# sousvide2.net
KiCad netlist of a schematic drawn in EAGLE
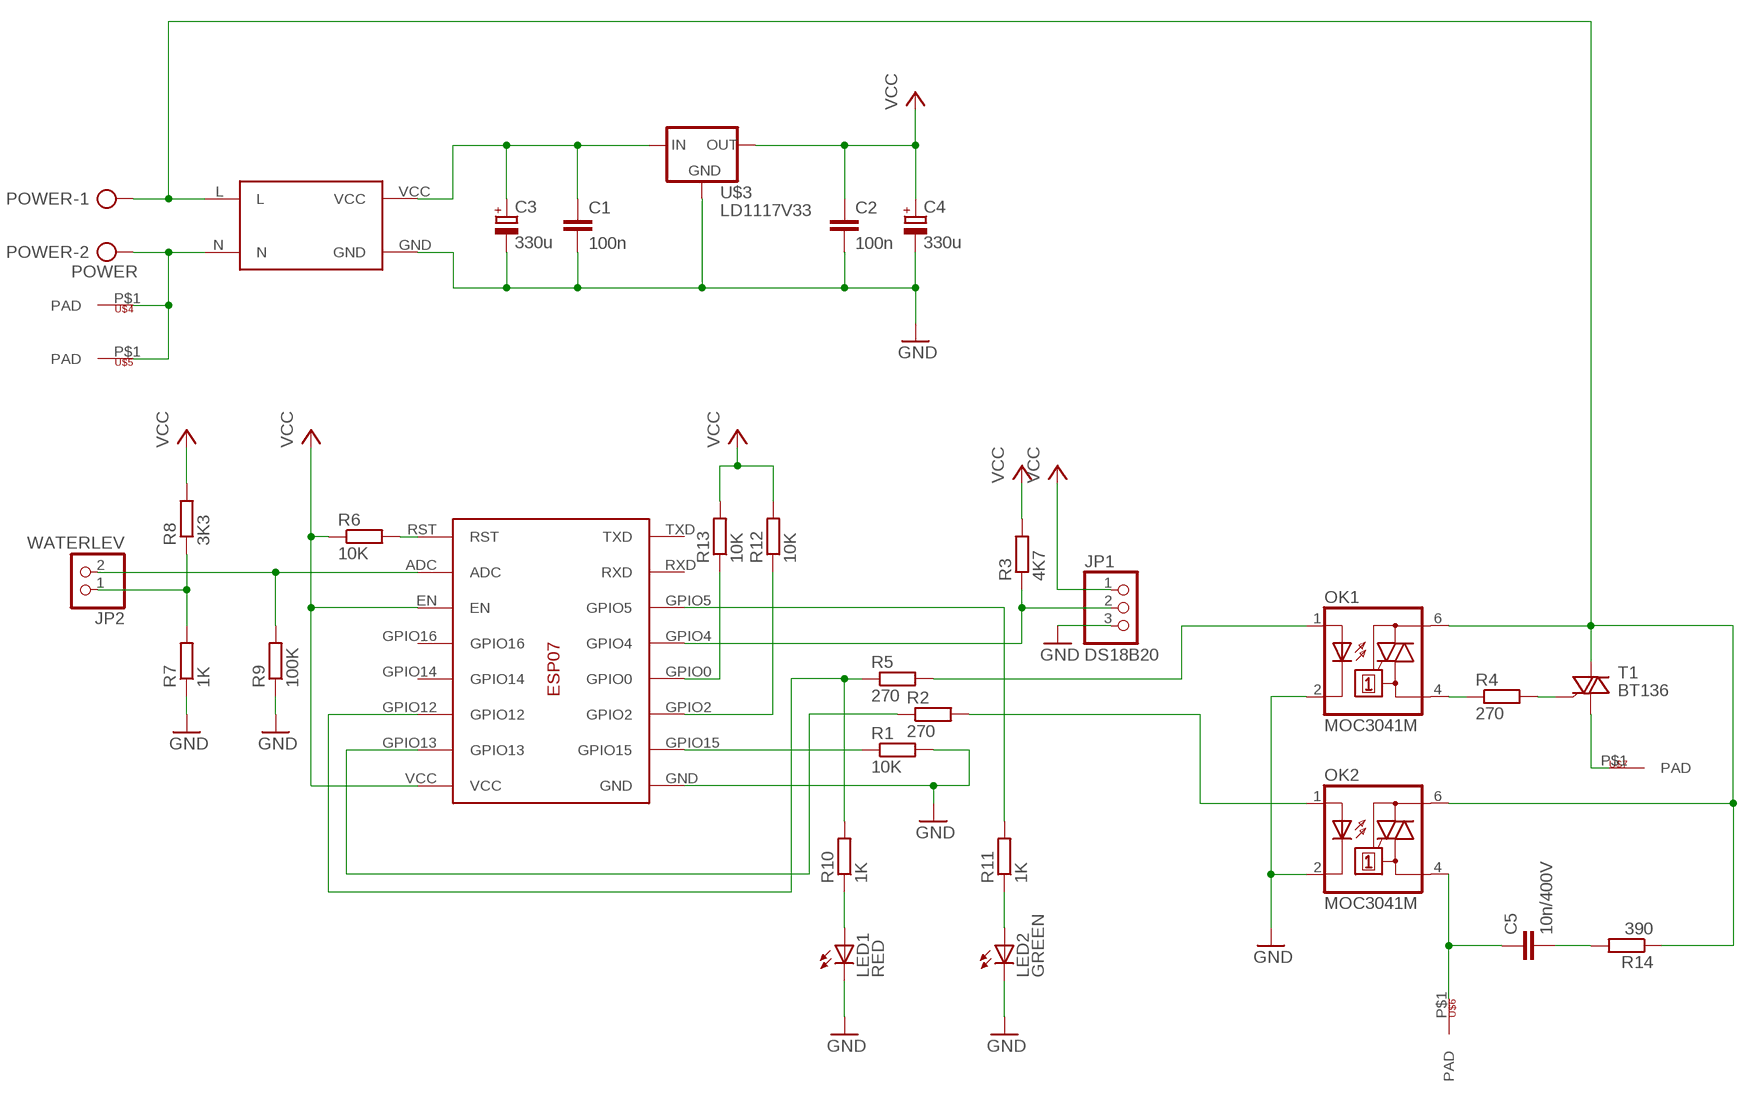
[diagram p0: schematic, sheet 1]

(export (version "E")
  (design (tool "Eeschema 10.0.6"))
  (components
    (comp (ref "C1")
      (value "100n")
      (footprint "eagle-import:C050-025X075")
      (libsource (lib "eagle-import") (part "C-EU050-025X075"))
    )
    (comp (ref "C2")
      (value "100n")
      (footprint "eagle-import:C050-025X075")
      (libsource (lib "eagle-import") (part "C-EU050-025X075"))
    )
    (comp (ref "C3")
      (value "330u")
      (footprint "eagle-import:E2,5-6")
      (libsource (lib "eagle-import") (part "CPOL-EUE2.5-6"))
    )
    (comp (ref "C4")
      (value "330u")
      (footprint "eagle-import:E2,5-6")
      (libsource (lib "eagle-import") (part "CPOL-EUE2.5-6"))
    )
    (comp (ref "C5")
      (value "10n/400V")
      (footprint "eagle-import:C102-064X133")
      (libsource (lib "eagle-import") (part "resistor_C-EU102-064X133"))
    )
    (comp (ref "JP1")
      (value "DS18B20")
      (footprint "eagle-import:1X03")
      (libsource (lib "eagle-import") (part "PINHD-1X3"))
    )
    (comp (ref "JP2")
      (value "WATERLEV")
      (footprint "eagle-import:1X02")
      (libsource (lib "eagle-import") (part "PINHD-1X2"))
    )
    (comp (ref "LED1")
      (value "RED")
      (footprint "eagle-import:LED5MM")
      (libsource (lib "eagle-import") (part "LED5MM"))
    )
    (comp (ref "LED2")
      (value "GREEN")
      (footprint "eagle-import:LED5MM")
      (libsource (lib "eagle-import") (part "LED5MM"))
    )
    (comp (ref "OK1")
      (value "MOC3041M")
      (footprint "eagle-import:DIL06")
      (fields (field (name "MF") "FAIRCHILD SEMICONDUCTOR"))
      (libsource (lib "eagle-import") (part "MOC3041M"))
    )
    (comp (ref "OK2")
      (value "MOC3041M")
      (footprint "eagle-import:DIL06")
      (fields (field (name "MF") "FAIRCHILD SEMICONDUCTOR"))
      (libsource (lib "eagle-import") (part "MOC3041M"))
    )
    (comp (ref "POWER")
      (value "POWER")
      (footprint "eagle-import:AK300_2")
      (libsource (lib "eagle-import") (part "AK300/2"))
    )
    (comp (ref "R1")
      (value "10K")
      (footprint "eagle-import:0204_7")
      (libsource (lib "eagle-import") (part "R-EU_0204/7"))
    )
    (comp (ref "R2")
      (value "270")
      (footprint "eagle-import:0204_7")
      (libsource (lib "eagle-import") (part "R-EU_0204/7"))
    )
    (comp (ref "R3")
      (value "4K7")
      (footprint "eagle-import:0204_7")
      (libsource (lib "eagle-import") (part "R-EU_0204/7"))
    )
    (comp (ref "R4")
      (value "270")
      (footprint "eagle-import:0204_7")
      (libsource (lib "eagle-import") (part "R-EU_0204/7"))
    )
    (comp (ref "R5")
      (value "270")
      (footprint "eagle-import:0207_12")
      (libsource (lib "eagle-import") (part "R-EU_0207/12"))
    )
    (comp (ref "R6")
      (value "10K")
      (footprint "eagle-import:0204_7")
      (libsource (lib "eagle-import") (part "R-EU_0204/7"))
    )
    (comp (ref "R7")
      (value "1K")
      (footprint "eagle-import:0204_7")
      (libsource (lib "eagle-import") (part "R-EU_0204/7"))
    )
    (comp (ref "R8")
      (value "3K3")
      (footprint "eagle-import:0204_7")
      (libsource (lib "eagle-import") (part "R-EU_0204/7"))
    )
    (comp (ref "R9")
      (value "100K")
      (footprint "eagle-import:0204_7")
      (libsource (lib "eagle-import") (part "R-EU_0204/7"))
    )
    (comp (ref "R10")
      (value "1K")
      (footprint "eagle-import:0204_7")
      (libsource (lib "eagle-import") (part "R-EU_0204/7"))
    )
    (comp (ref "R11")
      (value "1K")
      (footprint "eagle-import:0207_10")
      (libsource (lib "eagle-import") (part "R-EU_0207/10"))
    )
    (comp (ref "R12")
      (value "10K")
      (footprint "eagle-import:0204_7")
      (libsource (lib "eagle-import") (part "R-EU_0204/7"))
    )
    (comp (ref "R13")
      (value "10K")
      (footprint "eagle-import:0204_7")
      (libsource (lib "eagle-import") (part "R-EU_0204/7"))
    )
    (comp (ref "R14")
      (value "390")
      (footprint "eagle-import:0207_7")
      (libsource (lib "eagle-import") (part "R-EU_0207/7"))
    )
    (comp (ref "T1")
      (value "BT136")
      (footprint "eagle-import:TO220AB")
      (libsource (lib "eagle-import") (part "BT136"))
    )
    (comp (ref "U$1")
      (value "ESP12F")
      (footprint "eagle-import:ESP07")
      (libsource (lib "eagle-import") (part "ESP07"))
    )
    (comp (ref "U$2")
      (value "PSU5V1A")
      (footprint "eagle-import:PSU5V")
      (libsource (lib "eagle-import") (part "PSU5V1A"))
    )
    (comp (ref "U$3")
      (value "LD1117V33")
      (footprint "eagle-import:LD1117V33")
      (libsource (lib "eagle-import") (part "LD1117V33"))
    )
    (comp (ref "U$4")
      (value "PAD")
      (footprint "eagle-import:PAD")
      (libsource (lib "eagle-import") (part "PAD"))
    )
    (comp (ref "U$5")
      (value "PAD")
      (footprint "eagle-import:PAD")
      (libsource (lib "eagle-import") (part "PAD"))
    )
    (comp (ref "U$6")
      (value "PAD")
      (footprint "eagle-import:PAD")
      (libsource (lib "eagle-import") (part "PAD"))
    )
    (comp (ref "U$7")
      (value "PAD")
      (footprint "eagle-import:PAD")
      (libsource (lib "eagle-import") (part "PAD"))
    )
  )
  (nets
    (net (code "1") (name "GND") (class "Default")
      (node (ref "C1") (pin "2") (pinfunction "2_2") (pintype "passive"))
      (node (ref "C2") (pin "2") (pinfunction "2_2") (pintype "passive"))
      (node (ref "C3") (pin "-") (pinfunction "-_-") (pintype "passive"))
      (node (ref "C4") (pin "-") (pinfunction "-_-") (pintype "passive"))
      (node (ref "JP1") (pin "3") (pinfunction "3_3") (pintype "passive"))
      (node (ref "LED1") (pin "K") (pinfunction "C_K") (pintype "passive"))
      (node (ref "LED2") (pin "K") (pinfunction "C_K") (pintype "passive"))
      (node (ref "OK1") (pin "2") (pinfunction "C_2") (pintype "passive"))
      (node (ref "OK2") (pin "2") (pinfunction "C_2") (pintype "passive"))
      (node (ref "R1") (pin "2") (pinfunction "2_2") (pintype "passive"))
      (node (ref "R7") (pin "1") (pinfunction "1_1") (pintype "passive"))
      (node (ref "R9") (pin "1") (pinfunction "1_1") (pintype "passive"))
      (node (ref "U$1") (pin "GND") (pinfunction "GND_GND") (pintype "bidirectional"))
      (node (ref "U$2") (pin "GND") (pinfunction "GND_GND") (pintype "bidirectional"))
      (node (ref "U$3") (pin "GND") (pinfunction "GND_GND") (pintype "input"))
    )
    (net (code "2") (name "Net-(C1-Pad1)") (class "Default")
      (node (ref "C1") (pin "1") (pinfunction "1_1") (pintype "passive"))
      (node (ref "C3") (pin "+") (pinfunction "+_+") (pintype "passive"))
      (node (ref "U$2") (pin "VCC") (pinfunction "VCC_VCC") (pintype "bidirectional"))
      (node (ref "U$3") (pin "IN") (pinfunction "IN_IN") (pintype "input"))
    )
    (net (code "3") (name "Net-(C5-Pad2)") (class "Default")
      (node (ref "C5") (pin "2") (pinfunction "2_2") (pintype "passive"))
      (node (ref "R14") (pin "2") (pinfunction "2_2") (pintype "passive"))
    )
    (net (code "4") (name "Net-(JP1-Pad2)") (class "Default")
      (node (ref "JP1") (pin "2") (pinfunction "2_2") (pintype "passive"))
      (node (ref "R3") (pin "1") (pinfunction "1_1") (pintype "passive"))
      (node (ref "U$1") (pin "GPIO4") (pinfunction "GPIO4_GPIO4") (pintype "bidirectional"))
    )
    (net (code "5") (name "Net-(JP2-Pad1)") (class "Default")
      (node (ref "JP2") (pin "1") (pinfunction "1_1") (pintype "passive"))
      (node (ref "R7") (pin "2") (pinfunction "2_2") (pintype "passive"))
      (node (ref "R8") (pin "1") (pinfunction "1_1") (pintype "passive"))
    )
    (net (code "6") (name "Net-(JP2-Pad2)") (class "Default")
      (node (ref "JP2") (pin "2") (pinfunction "2_2") (pintype "passive"))
      (node (ref "R9") (pin "2") (pinfunction "2_2") (pintype "passive"))
      (node (ref "U$1") (pin "ADC") (pinfunction "ADC_ADC") (pintype "bidirectional"))
    )
    (net (code "7") (name "Net-(LED1-PadA)") (class "Default")
      (node (ref "LED1") (pin "A") (pinfunction "A_A") (pintype "passive"))
      (node (ref "R10") (pin "1") (pinfunction "1_1") (pintype "passive"))
    )
    (net (code "8") (name "Net-(LED2-PadA)") (class "Default")
      (node (ref "LED2") (pin "A") (pinfunction "A_A") (pintype "passive"))
      (node (ref "R11") (pin "1") (pinfunction "1_1") (pintype "passive"))
    )
    (net (code "9") (name "Net-(OK1-A)") (class "Default")
      (node (ref "OK1") (pin "1") (pinfunction "A_1") (pintype "passive"))
      (node (ref "R5") (pin "2") (pinfunction "2_2") (pintype "passive"))
    )
    (net (code "10") (name "Net-(OK1-A1)") (class "Default")
      (node (ref "OK1") (pin "4") (pinfunction "A1_4") (pintype "passive"))
      (node (ref "R4") (pin "1") (pinfunction "1_1") (pintype "passive"))
    )
    (net (code "11") (name "Net-(OK1-A2)") (class "Default")
      (node (ref "OK1") (pin "6") (pinfunction "A2_6") (pintype "passive"))
      (node (ref "OK2") (pin "6") (pinfunction "A2_6") (pintype "passive"))
      (node (ref "POWER") (pin "1") (pinfunction "KL_1") (pintype "passive"))
      (node (ref "R14") (pin "1") (pinfunction "1_1") (pintype "passive"))
      (node (ref "T1") (pin "2") (pinfunction "A2_2") (pintype "passive"))
      (node (ref "U$2") (pin "L") (pinfunction "L_L") (pintype "bidirectional"))
    )
    (net (code "12") (name "Net-(OK2-A)") (class "Default")
      (node (ref "OK2") (pin "1") (pinfunction "A_1") (pintype "passive"))
      (node (ref "R2") (pin "2") (pinfunction "2_2") (pintype "passive"))
    )
    (net (code "13") (name "Net-(OK2-A1)") (class "Default")
      (node (ref "C5") (pin "1") (pinfunction "1_1") (pintype "passive"))
      (node (ref "OK2") (pin "4") (pinfunction "A1_4") (pintype "passive"))
      (node (ref "U$6") (pin "P$1") (pinfunction "PAD_P$1") (pintype "bidirectional"))
    )
    (net (code "14") (name "Net-(POWERB-KL)") (class "Default")
      (node (ref "POWER") (pin "2") (pinfunction "KL_2") (pintype "passive"))
      (node (ref "U$2") (pin "N") (pinfunction "N_N") (pintype "bidirectional"))
      (node (ref "U$4") (pin "P$1") (pinfunction "PAD_P$1") (pintype "bidirectional"))
      (node (ref "U$5") (pin "P$1") (pinfunction "PAD_P$1") (pintype "bidirectional"))
    )
    (net (code "15") (name "Net-(R1-Pad1)") (class "Default")
      (node (ref "R1") (pin "1") (pinfunction "1_1") (pintype "passive"))
      (node (ref "U$1") (pin "GPIO15") (pinfunction "GPIO15_GPIO15") (pintype "bidirectional"))
    )
    (net (code "16") (name "Net-(R2-Pad1)") (class "Default")
      (node (ref "R2") (pin "1") (pinfunction "1_1") (pintype "passive"))
      (node (ref "U$1") (pin "GPIO13") (pinfunction "GPIO13_GPIO13") (pintype "bidirectional"))
    )
    (net (code "17") (name "Net-(R6-Pad2)") (class "Default")
      (node (ref "R6") (pin "2") (pinfunction "2_2") (pintype "passive"))
      (node (ref "U$1") (pin "RST") (pinfunction "RST_RST") (pintype "bidirectional"))
    )
    (net (code "18") (name "Net-(R10-Pad2)") (class "Default")
      (node (ref "R10") (pin "2") (pinfunction "2_2") (pintype "passive"))
      (node (ref "R5") (pin "1") (pinfunction "1_1") (pintype "passive"))
      (node (ref "U$1") (pin "GPIO12") (pinfunction "GPIO12_GPIO12") (pintype "bidirectional"))
    )
    (net (code "19") (name "Net-(R11-Pad2)") (class "Default")
      (node (ref "R11") (pin "2") (pinfunction "2_2") (pintype "passive"))
      (node (ref "U$1") (pin "GPIO5") (pinfunction "GPIO5_GPIO5") (pintype "bidirectional"))
    )
    (net (code "20") (name "Net-(R12-Pad1)") (class "Default")
      (node (ref "R12") (pin "1") (pinfunction "1_1") (pintype "passive"))
      (node (ref "U$1") (pin "GPIO2") (pinfunction "GPIO2_GPIO2") (pintype "bidirectional"))
    )
    (net (code "21") (name "Net-(R13-Pad1)") (class "Default")
      (node (ref "R13") (pin "1") (pinfunction "1_1") (pintype "passive"))
      (node (ref "U$1") (pin "GPIO0") (pinfunction "GPIO0_GPIO0") (pintype "bidirectional"))
    )
    (net (code "22") (name "Net-(T1-A1)") (class "Default")
      (node (ref "T1") (pin "1") (pinfunction "A1_1") (pintype "passive"))
      (node (ref "U$7") (pin "P$1") (pinfunction "PAD_P$1") (pintype "bidirectional"))
    )
    (net (code "23") (name "Net-(T1-G)") (class "Default")
      (node (ref "R4") (pin "2") (pinfunction "2_2") (pintype "passive"))
      (node (ref "T1") (pin "3") (pinfunction "G_3") (pintype "passive"))
    )
    (net (code "24") (name "VCC") (class "Default")
      (node (ref "C2") (pin "1") (pinfunction "1_1") (pintype "passive"))
      (node (ref "C4") (pin "+") (pinfunction "+_+") (pintype "passive"))
      (node (ref "JP1") (pin "1") (pinfunction "1_1") (pintype "passive"))
      (node (ref "R12") (pin "2") (pinfunction "2_2") (pintype "passive"))
      (node (ref "R13") (pin "2") (pinfunction "2_2") (pintype "passive"))
      (node (ref "R3") (pin "2") (pinfunction "2_2") (pintype "passive"))
      (node (ref "R6") (pin "1") (pinfunction "1_1") (pintype "passive"))
      (node (ref "R8") (pin "2") (pinfunction "2_2") (pintype "passive"))
      (node (ref "U$1") (pin "EN") (pinfunction "EN_EN") (pintype "bidirectional"))
      (node (ref "U$1") (pin "VCC") (pinfunction "VCC_VCC") (pintype "bidirectional"))
      (node (ref "U$3") (pin "OUT") (pinfunction "OUT_OUT") (pintype "output"))
    )
    (net (code "25") (name "unconnected-(U$1-PadGPIO14)") (class "Default")
      (node (ref "U$1") (pin "GPIO14") (pinfunction "GPIO14_GPIO14") (pintype "bidirectional"))
    )
    (net (code "26") (name "unconnected-(U$1-PadGPIO16)") (class "Default")
      (node (ref "U$1") (pin "GPIO16") (pinfunction "GPIO16_GPIO16") (pintype "bidirectional"))
    )
    (net (code "27") (name "unconnected-(U$1-PadRXD)") (class "Default")
      (node (ref "U$1") (pin "RXD") (pinfunction "RXD_RXD") (pintype "bidirectional"))
    )
    (net (code "28") (name "unconnected-(U$1-PadTXD)") (class "Default")
      (node (ref "U$1") (pin "TXD") (pinfunction "TXD_TXD") (pintype "bidirectional"))
    )
  )
)
